# Audio.net
KiCad netlist of a schematic drawn in Altium Designer
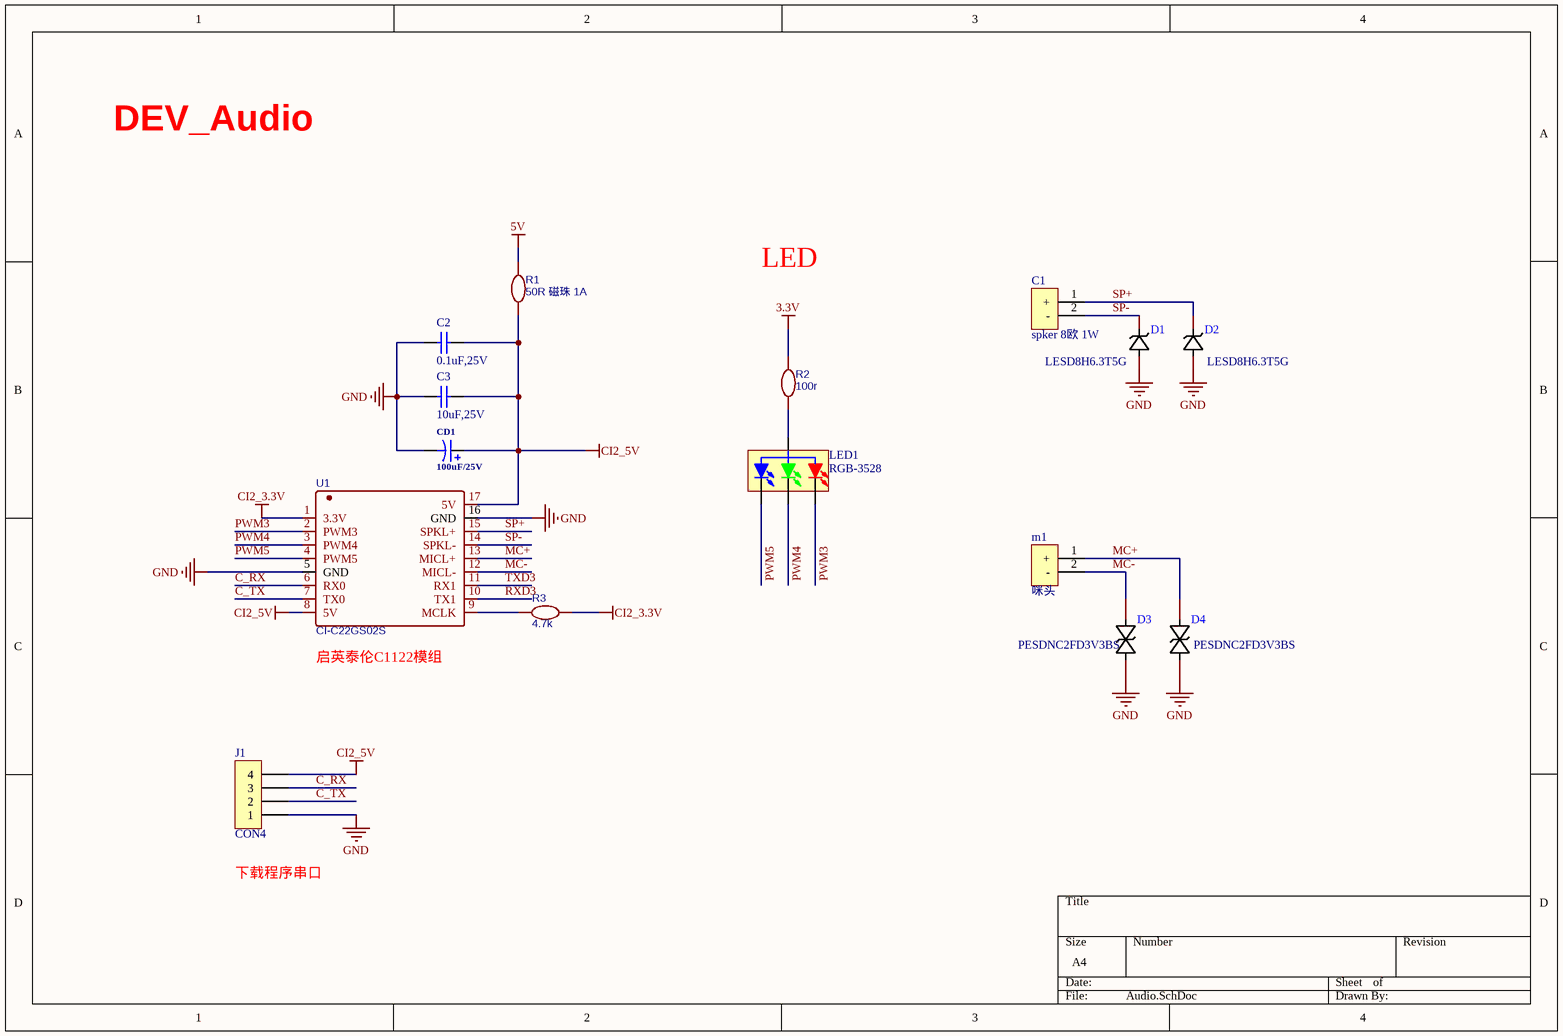
[diagram p0: Audio.SchDoc]

(export (version "E")
  (design (tool "Eeschema 10.0.6"))
  (components
    (comp (ref "C1")
      (value "spker 8欧 1W")
      (footprint "XH2.54A-2")
      (libsource (lib "Schlib_PICO") (part "SPK"))
    )
    (comp (ref "C2")
      (value "0.1uF,25V")
      (footprint "0402_C")
      (description "贴片电容")
      (fields (field (name "PART NUMBER") "T_Cap_0603_0.1uF_25V_X5R") (field (name "TOLERANCE") "10%"))
      (libsource (lib "Database_Library") (part "Cap"))
    )
    (comp (ref "C3")
      (value "10uF,25V")
      (footprint "0402_C")
      (description "贴片电容")
      (fields (field (name "PART NUMBER") "T_Cap_0603_0.1uF_25V_X5R") (field (name "TOLERANCE") "10%"))
      (libsource (lib "Database_Library") (part "Cap"))
    )
    (comp (ref "CD1")
      (value "100uF/25V")
      (footprint "CD7343")
      (description "钽电容,Tantalum Capacitors,47uF/16V,3.5*2.8")
      (fields (field (name "PUBLISHER") "Altium Limited"))
      (libsource (lib "模拟器件") (part "C-100uF/25V"))
    )
    (comp (ref "D1")
      (value "LESD8H6.3T5G")
      (footprint "SOD-882_L1.0-W0.6-R-RD")
      (fields (field (name "MANUFACTURER") "LRC(乐山无线电)"))
      (libsource (lib "SN_Schlib") (part "LESD8H6.3T5G"))
    )
    (comp (ref "D2")
      (value "LESD8H6.3T5G")
      (footprint "SOD-882_L1.0-W0.6-R-RD")
      (fields (field (name "MANUFACTURER") "LRC(乐山无线电)"))
      (libsource (lib "SN_Schlib") (part "LESD8H6.3T5G"))
    )
    (comp (ref "D3")
      (value "PESDNC2FD3V3BS")
      (footprint "DFN1006-2L-BI")
      (fields (field (name "MANUFACTURER") "LRC(乐山无线电)") (field (name "MANUFACTURER PART") "LESD8H6.3T5G"))
      (libsource (lib "SN_Schlib") (part "PESDNC2FD3V3BS"))
    )
    (comp (ref "D4")
      (value "PESDNC2FD3V3BS")
      (footprint "DFN1006-2L-BI")
      (fields (field (name "MANUFACTURER") "LRC(乐山无线电)") (field (name "MANUFACTURER PART") "LESD8H6.3T5G"))
      (libsource (lib "SN_Schlib") (part "PESDNC2FD3V3BS"))
    )
    (comp (ref "J1") (value "CON4") (description "Connector") (libsource (lib "Schlib1") (part "CON4")))
    (comp (ref "LED1")
      (value "RGB-3528")
      (footprint "LED-TH_4P-BD6.9-P1.27-R")
      (description "三基色LED")
      (fields (field (name "版权归属") "源创客"))
      (libsource (lib "Schlib_PICO") (part "LED-RGB-3528"))
    )
    (comp (ref "m1")
      (value "咪头")
      (footprint "MIC-TH_BD6.0-P1.90-D0.4-L-RD")
      (libsource (lib "Schlib_PICO") (part "mic"))
    )
    (comp (ref "R1")
      (value "50R 磁珠 1A")
      (footprint "0402_R")
      (fields (field (name "CONTRIBUTOR") "LCEDA_Lib"))
      (libsource (lib "altium-import") (part "root_1_100k_"))
    )
    (comp (ref "R2")
      (value "100r")
      (footprint "0402_R")
      (fields (field (name "CONTRIBUTOR") "LCEDA_Lib"))
      (libsource (lib "altium-import") (part "root_1_100k_"))
    )
    (comp (ref "R3")
      (value "4.7k")
      (footprint "0402_R")
      (fields (field (name "CONTRIBUTOR") "LCEDA_Lib"))
      (libsource (lib "altium-import") (part "root_2_100k_"))
    )
    (comp (ref "U1")
      (value "CI-C22GS02S")
      (footprint "SMD-17_L20.0-W1.80-CI-C22GS02S")
      (fields (field (name "BOM_SUPPLIER PART") "C2759836") (field (name "CONTRIBUTOR") "LCSC"))
      (libsource (lib "Schlib_PICO") (part "CI-C22GS02S"))
    )
  )
  (nets
    (net (code "1") (name "/C_RX") (class "Default")
      (node (ref "J1") (pin "3") (pinfunction "3_3") (pintype "passive"))
      (node (ref "U1") (pin "6") (pinfunction "RX0_6") (pintype "passive"))
    )
    (net (code "2") (name "/C_TX") (class "Default")
      (node (ref "J1") (pin "2") (pinfunction "2_2") (pintype "passive"))
      (node (ref "U1") (pin "7") (pinfunction "TX0_7") (pintype "passive"))
    )
    (net (code "3") (name "/MC+") (class "Default")
      (node (ref "D4") (pin "1") (pinfunction "A_1") (pintype "passive"))
      (node (ref "U1") (pin "13") (pinfunction "MICL+_13") (pintype "passive"))
      (node (ref "m1") (pin "1") (pinfunction "+_1") (pintype "passive"))
    )
    (net (code "4") (name "/MC-") (class "Default")
      (node (ref "D3") (pin "1") (pinfunction "A_1") (pintype "passive"))
      (node (ref "U1") (pin "12") (pinfunction "MICL-_12") (pintype "passive"))
      (node (ref "m1") (pin "2") (pinfunction "-_2") (pintype "passive"))
    )
    (net (code "5") (name "/PWM3") (class "Default")
      (node (ref "LED1") (pin "1") (pinfunction "RED_K_1") (pintype "passive"))
      (node (ref "U1") (pin "2") (pinfunction "PWM3_2") (pintype "passive"))
    )
    (net (code "6") (name "/PWM4") (class "Default")
      (node (ref "LED1") (pin "3") (pinfunction "GREEN_K_3") (pintype "passive"))
      (node (ref "U1") (pin "3") (pinfunction "PWM4_3") (pintype "passive"))
    )
    (net (code "7") (name "/PWM5") (class "Default")
      (node (ref "LED1") (pin "4") (pinfunction "BULE_K_4") (pintype "passive"))
      (node (ref "U1") (pin "4") (pinfunction "PWM5_4") (pintype "passive"))
    )
    (net (code "8") (name "/RXD3") (class "Default")
      (node (ref "U1") (pin "10") (pinfunction "TX1_10") (pintype "passive"))
    )
    (net (code "9") (name "/SP+") (class "Default")
      (node (ref "C1") (pin "1") (pinfunction "+_1") (pintype "passive"))
      (node (ref "D2") (pin "2") (pinfunction "K_2") (pintype "passive"))
      (node (ref "U1") (pin "15") (pinfunction "SPKL+_15") (pintype "passive"))
    )
    (net (code "10") (name "/SP-") (class "Default")
      (node (ref "C1") (pin "2") (pinfunction "-_2") (pintype "passive"))
      (node (ref "D1") (pin "2") (pinfunction "K_2") (pintype "passive"))
      (node (ref "U1") (pin "14") (pinfunction "SPKL-_14") (pintype "passive"))
    )
    (net (code "11") (name "/TXD3") (class "Default")
      (node (ref "U1") (pin "11") (pinfunction "RX1_11") (pintype "passive"))
    )
    (net (code "12") (name "3.3V") (class "Default")
      (node (ref "R2") (pin "2") (pinfunction "2_2") (pintype "passive"))
    )
    (net (code "13") (name "5V") (class "Default")
      (node (ref "R1") (pin "2") (pinfunction "2_2") (pintype "passive"))
    )
    (net (code "14") (name "CI2_3.3V") (class "Default")
      (node (ref "R3") (pin "1") (pinfunction "1_1") (pintype "passive"))
      (node (ref "U1") (pin "1") (pinfunction "3.3V_1") (pintype "passive"))
    )
    (net (code "15") (name "CI2_5V") (class "Default")
      (node (ref "C2") (pin "1") (pinfunction "1_1") (pintype "passive"))
      (node (ref "C3") (pin "1") (pinfunction "1_1") (pintype "passive"))
      (node (ref "CD1") (pin "1") (pinfunction "1_1") (pintype "passive"))
      (node (ref "J1") (pin "4") (pinfunction "4_4") (pintype "passive"))
      (node (ref "R1") (pin "1") (pinfunction "1_1") (pintype "passive"))
      (node (ref "U1") (pin "17") (pinfunction "5V_17") (pintype "passive"))
      (node (ref "U1") (pin "8") (pinfunction "5V_8") (pintype "passive"))
    )
    (net (code "16") (name "GND") (class "Default")
      (node (ref "C2") (pin "2") (pinfunction "2_2") (pintype "passive"))
      (node (ref "C3") (pin "2") (pinfunction "2_2") (pintype "passive"))
      (node (ref "CD1") (pin "2") (pinfunction "2_2") (pintype "passive"))
      (node (ref "D1") (pin "1") (pinfunction "A_1") (pintype "passive"))
      (node (ref "D2") (pin "1") (pinfunction "A_1") (pintype "passive"))
      (node (ref "D3") (pin "2") (pinfunction "K_2") (pintype "passive"))
      (node (ref "D4") (pin "2") (pinfunction "K_2") (pintype "passive"))
      (node (ref "J1") (pin "1") (pinfunction "1_1") (pintype "passive"))
      (node (ref "U1") (pin "16") (pinfunction "GND_16") (pintype "passive"))
      (node (ref "U1") (pin "5") (pinfunction "GND_5") (pintype "passive"))
    )
    (net (code "17") (name "Net-(LED1-A)") (class "Default")
      (node (ref "LED1") (pin "2") (pinfunction "A_2") (pintype "passive"))
      (node (ref "R2") (pin "1") (pinfunction "1_1") (pintype "passive"))
    )
    (net (code "18") (name "Net-(U1-MCLK)") (class "Default")
      (node (ref "R3") (pin "2") (pinfunction "2_2") (pintype "passive"))
      (node (ref "U1") (pin "9") (pinfunction "MCLK_9") (pintype "passive"))
    )
  )
)
